# POWER_GEN.net
KiCad netlist of a schematic drawn in Altium Designer
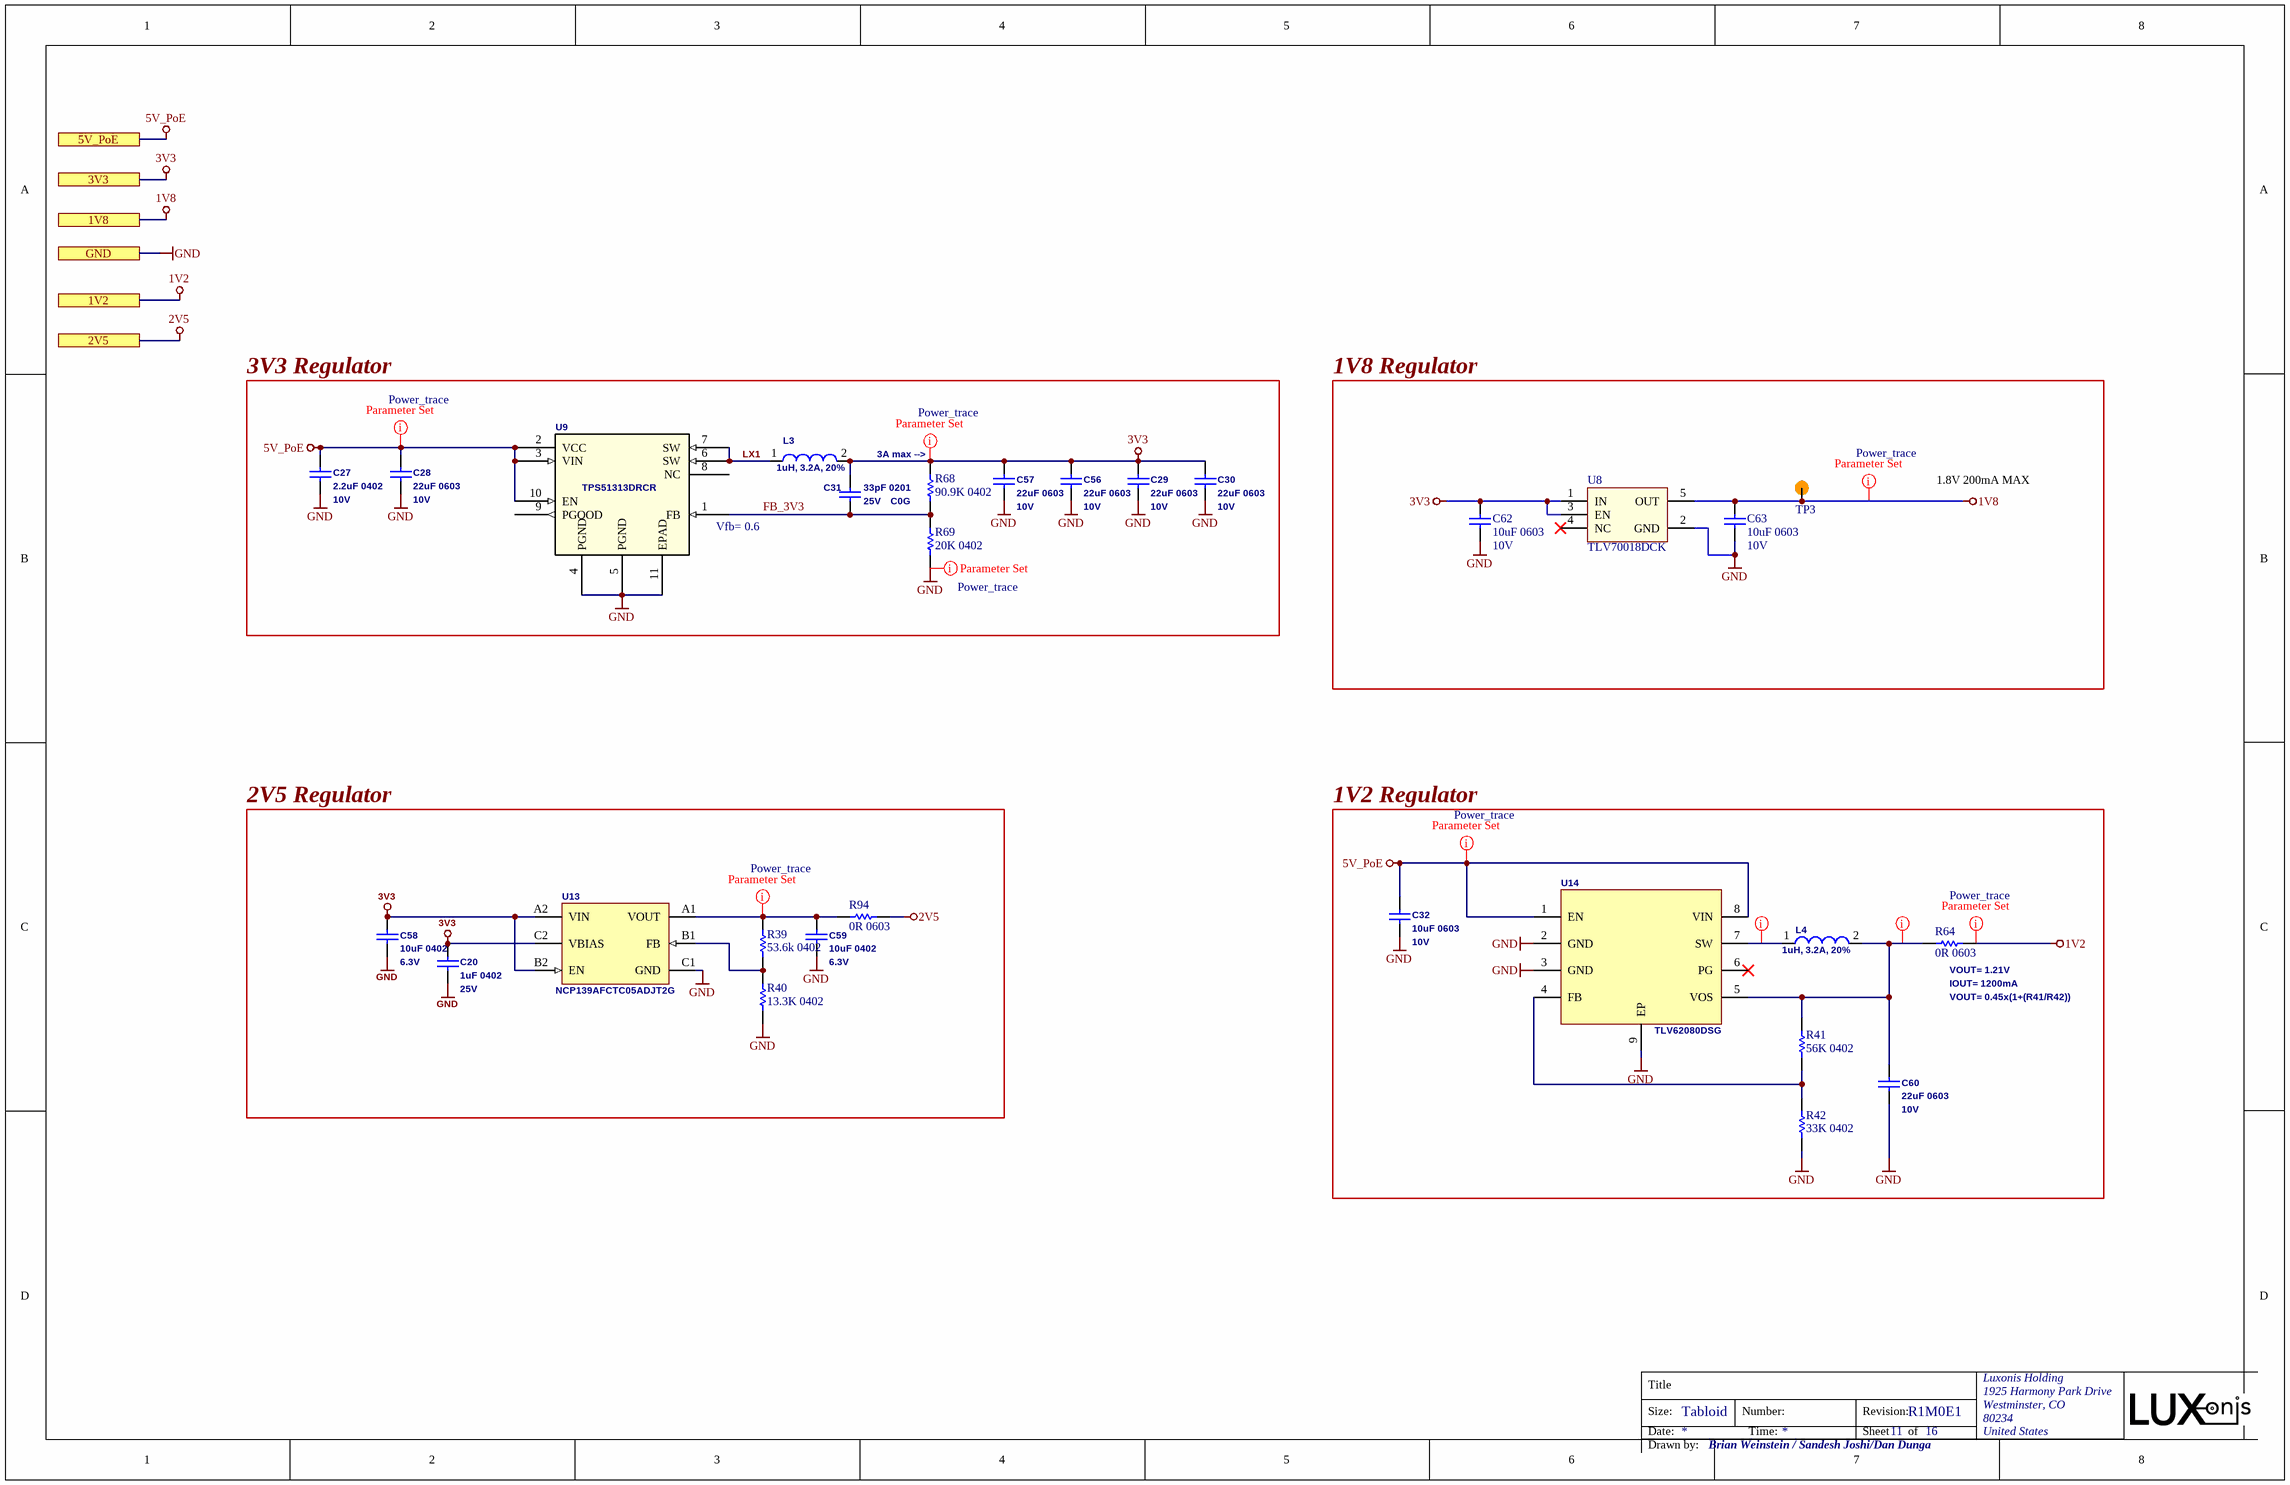
[diagram p0: POWER_GEN.SchDoc]

(export (version "E")
  (design (tool "Eeschema 10.0.6"))
  (components
    (comp (ref "C20")
      (value "1uF 0402")
      (footprint "CAP_Altium_Vault_Generic:CAPC0402(1005)70_L")
      (description "CAP CER 1UF 25V X5R 0402 10%")
      (fields
        (field (name "TOLERANCE") "10%")
        (field (name "VOLTAGE RATING") "25V")
        (field (name "VOLTAGE") "25V")
      )
      (libsource (lib "LuxonisMaster") (part "GRM155R61E105KA12D"))
    )
    (comp (ref "C27")
      (value "2.2uF 0402")
      (footprint "CAP_Altium_Vault_Generic:CAPC0402(1005)70_L")
      (description "CAP CER 2.2UF 10V X5R 0402 10%")
      (fields (field (name "TOLERANCE") "10%") (field (name "VOLTAGE RATING") "10V"))
      (libsource (lib "LuxonisMaster") (part "GRM155R61A225KE95D"))
    )
    (comp (ref "C28")
      (value "22uF 0603")
      (footprint "CAP_Altium_Vault_Generic:CAPC0603(1608)100_L")
      (description "CAP CER 22UF 10V X5R 0603 20%")
      (fields (field (name "TOLERANCE") "20%") (field (name "VOLTAGE RATING") "10V"))
      (libsource (lib "LuxonisMaster") (part "GRM188R61A226ME15D"))
    )
    (comp (ref "C29")
      (value "22uF 0603")
      (footprint "CAP_Altium_Vault_Generic:CAPC0603(1608)100_L")
      (description "CAP CER 22UF 10V X5R 0603 20%")
      (fields (field (name "TOLERANCE") "20%") (field (name "VOLTAGE RATING") "10V"))
      (libsource (lib "LuxonisMaster") (part "GRM188R61A226ME15D"))
    )
    (comp (ref "C30")
      (value "22uF 0603")
      (footprint "CAP_Altium_Vault_Generic:CAPC0603(1608)100_L")
      (description "CAP CER 22UF 10V X5R 0603 20%")
      (fields (field (name "TOLERANCE") "20%") (field (name "VOLTAGE RATING") "10V"))
      (libsource (lib "LuxonisMaster") (part "GRM188R61A226ME15D"))
    )
    (comp (ref "C31")
      (value "33pF 0201")
      (footprint "CAP_Altium_Vault_Generic:CAPC0201(0603)33_L")
      (description "CAP CER 33PF 25V C0G/NP0 0201")
      (fields
        (field (name "TOLERANCE") "5%")
        (field (name "VOLTAGE RATING") "25V")
        (field (name "DIELECTRIC") "C0G")
      )
      (libsource (lib "LuxonisMaster") (part "GRM0335C1E330JA01D"))
    )
    (comp (ref "C32")
      (value "10uF 0603")
      (footprint "CAP_Altium_Vault_Generic:CAPC0603(1608)100_L")
      (description "CAP CER 10UF 10V X5R 0603 20%")
      (fields (field (name "TOLERANCE") "20%") (field (name "VOLTAGE RATING") "10V"))
      (libsource (lib "LuxonisMaster") (part "GRM188R61A106ME69D"))
    )
    (comp (ref "C56")
      (value "22uF 0603")
      (footprint "CAP_Altium_Vault_Generic:CAPC0603(1608)100_L")
      (description "CAP CER 22UF 10V X5R 0603 20%")
      (fields (field (name "TOLERANCE") "20%") (field (name "VOLTAGE RATING") "10V"))
      (libsource (lib "LuxonisMaster") (part "GRM188R61A226ME15D"))
    )
    (comp (ref "C57")
      (value "22uF 0603")
      (footprint "CAP_Altium_Vault_Generic:CAPC0603(1608)100_L")
      (description "CAP CER 22UF 10V X5R 0603 20%")
      (fields (field (name "TOLERANCE") "20%") (field (name "VOLTAGE RATING") "10V"))
      (libsource (lib "LuxonisMaster") (part "GRM188R61A226ME15D"))
    )
    (comp (ref "C58")
      (value "10uF 0402")
      (footprint "CAP_Altium_Vault_Generic:CAPC0402(1005)70_L")
      (description "CAP CER 10UF 6.3V X5R 0402 20%")
      (fields (field (name "TOLERANCE") "20%") (field (name "VOLTAGE RATING") "6.3V"))
      (libsource (lib "LuxonisMaster") (part "GRM155R60J106ME15D"))
    )
    (comp (ref "C59")
      (value "10uF 0402")
      (footprint "CAP_Altium_Vault_Generic:CAPC0402(1005)70_L")
      (description "CAP CER 10UF 6.3V X5R 0402 20%")
      (fields (field (name "TOLERANCE") "20%") (field (name "VOLTAGE RATING") "6.3V"))
      (libsource (lib "LuxonisMaster") (part "GRM155R60J106ME15D"))
    )
    (comp (ref "C60")
      (value "22uF 0603")
      (footprint "CAP_Altium_Vault_Generic:CAPC0603(1608)100_L")
      (description "CAP CER 22UF 10V X5R 0603 20%")
      (fields (field (name "TOLERANCE") "20%") (field (name "VOLTAGE RATING") "10V"))
      (libsource (lib "LuxonisMaster") (part "GRM188R61A226ME15D"))
    )
    (comp (ref "C62")
      (value "10uF 0603")
      (footprint "CAP_Altium_Vault_Generic:CAPC0603(1608)100_N")
      (description "CAP CER 10UF 10V X5R 0603 20%")
      (fields (field (name "TOLERANCE") "20%") (field (name "VOLTAGE RATING") "10V"))
      (libsource (lib "LuxonisMaster") (part "GRM188R61A106ME69D"))
    )
    (comp (ref "C63")
      (value "10uF 0603")
      (footprint "CAP_Altium_Vault_Generic:CAPC0603(1608)100_N")
      (description "CAP CER 10UF 10V X5R 0603 20%")
      (fields (field (name "TOLERANCE") "20%") (field (name "VOLTAGE RATING") "10V"))
      (libsource (lib "LuxonisMaster") (part "GRM188R61A106ME69D"))
    )
    (comp (ref "L3")
      (value "1uH, 3.2A, 20%")
      (footprint "LuxonisMaster:DFE252012P-1R0M=P2")
      (description "FIXED IND 1UH 3.2A 42 MOHM SMD")
      (fields
        (field (name "MANUFACTURER") "Murata")
        (field (name "MANUFACTURER PART NUMBER") "DFE252012P-1R0M=P2")
      )
      (libsource (lib "LuxonisMaster") (part "DFE252012P-1R0M=P2"))
    )
    (comp (ref "L4")
      (value "1uH, 3.2A, 20%")
      (footprint "LuxonisMaster:DFE252012P-1R0M=P2")
      (description "FIXED IND 1UH 3.2A 42 MOHM SMD")
      (fields
        (field (name "MANUFACTURER") "Murata")
        (field (name "MANUFACTURER PART NUMBER") "DFE252012P-1R0M=P2")
      )
      (libsource (lib "LuxonisMaster") (part "DFE252012P-1R0M=P2"))
    )
    (comp (ref "R39")
      (value "53.6k 0402")
      (footprint "RES_Altium_Vault_Generic:RESC0402(1005)_L")
      (description "RES SMD 53.6K OHM 1% 1/16W 0402")
      (fields (field (name "TOLERANCE") "1%"))
      (libsource (lib "LuxonisMaster") (part "CRCW040253K6FKED"))
    )
    (comp (ref "R40")
      (value "13.3K 0402")
      (footprint "RES_Altium_Vault_Generic:RESC0402(1005)_L")
      (description "RES SMD 13.3K OHM 1% 1/16W 0402")
      (fields (field (name "TOLERANCE") "1%"))
      (libsource (lib "LuxonisMaster") (part "RC0402FR-0713K3L"))
    )
    (comp (ref "R41")
      (value "56K 0402")
      (footprint "RES_Altium_Vault_Generic:RESC0402(1005)_L")
      (fields
        (field (name "MANUFACTURER") "Yageo")
        (field (name "MANUFACTURER PART NUMBER") "RC0402FR-0756KL")
        (field (name "TOLERANCE") "1%")
      )
      (libsource (lib "LuxonisMaster") (part "RC0402FR-0756KL"))
    )
    (comp (ref "R42")
      (value "33K 0402")
      (footprint "RES_Altium_Vault_Generic:RESC0402(1005)_L")
      (description "RES SMD 33K OHM 1% 1/16W 0402")
      (fields (field (name "TOLERANCE") "1%"))
      (libsource (lib "LuxonisMaster") (part "CRCW040233K0FKED"))
    )
    (comp (ref "R64")
      (value "0R 0603")
      (footprint "RES_Altium_Vault_Generic:RESC0603(1608)_N")
      (description "RES SMD 0.0R OHM 1% 1/10W 0603")
      (fields (field (name "TOLERANCE") "5%"))
      (libsource (lib "LuxonisMaster") (part "CRCW06030000Z0EA"))
    )
    (comp (ref "R68")
      (value "90.9K 0402")
      (footprint "RES_Altium_Vault_Generic:RESC0402(1005)_L")
      (description "RES SMD 90.9K OHM 1% 1/16W 0402")
      (fields (field (name "TOLERANCE") "1%"))
      (libsource (lib "LuxonisMaster") (part "CRCW040290K9FKED"))
    )
    (comp (ref "R69")
      (value "20K 0402")
      (footprint "RES_Altium_Vault_Generic:RESC0402(1005)_L")
      (fields
        (field (name "MANUFACTURER") "Yageo")
        (field (name "MANUFACTURER PART NUMBER") "RC0402FR-0720KL")
        (field (name "TOLERANCE") "1%")
      )
      (libsource (lib "LuxonisMaster") (part "RC0402FR-0720KL"))
    )
    (comp (ref "R94")
      (value "0R 0603")
      (footprint "RES_Altium_Vault_Generic:RESC0603(1608)_N")
      (description "RES SMD 0.0R OHM 1% 1/10W 0603")
      (fields (field (name "TOLERANCE") "5%"))
      (libsource (lib "LuxonisMaster") (part "CRCW06030000Z0EA"))
    )
    (comp (ref "TP3")
      (value "TP100_200_NS")
      (footprint "TP100_200_NS")
      (libsource (lib "LuxonisMaster") (part "TEST_POINT"))
    )
    (comp (ref "U8")
      (value "TLV70018DCK")
      (footprint "TLV70018DCK")
      (description "IC REG LINEAR 1.8V 200MA SC70-5 Linear Voltage Regulator IC  1 Output  200mA SC-70-5")
      (libsource (lib "LuxonisMaster") (part "TLV70018DCK"))
    )
    (comp (ref "U9")
      (value "TPS51313DRCR")
      (footprint "VSON-TPS51313DRCR")
      (description "Switching Regulator, Voltage-mode, 3A, 1000kHz Switching Freq-Max, PDSO10")
      (libsource (lib "LuxonisMaster") (part "TPS51313DRCR"))
    )
    (comp (ref "U13")
      (value "NCP139AFCTC05ADJT2G")
      (footprint "NCP139AFCTC05ADJT2G")
      (description "IC REG LINEAR POS ADJ 1A 6WLCSP")
      (fields (field (name "OCTOPART") "https://octopart.com/ncp139afctc05adjt2g-on+semiconductor-77040756"))
      (libsource (lib "LuxonisMaster") (part "NCP139AFCTC05ADJT2G"))
    )
    (comp (ref "U14")
      (value "TLV62080DSG")
      (footprint "LuxonisMaster:TLV62080DSG")
      (description "IC REG BUCK ADJ 1.2A SYNC 8WSON")
      (libsource (lib "LuxonisMaster") (part "TLV62080DSG"))
    )
  )
  (nets
    (net (code "1") (name "/FB_3V3") (class "Default")
      (node (ref "C31") (pin "1") (pinfunction "1_1") (pintype "passive"))
      (node (ref "R68") (pin "1") (pinfunction "1_1") (pintype "passive"))
      (node (ref "R69") (pin "2") (pinfunction "2_2") (pintype "passive"))
      (node (ref "U9") (pin "1") (pinfunction "FB_1") (pintype "input"))
    )
    (net (code "2") (name "/LX1") (class "Default")
      (node (ref "L3") (pin "1") (pinfunction "1_1") (pintype "passive"))
      (node (ref "U9") (pin "6") (pinfunction "SW_6") (pintype "input"))
      (node (ref "U9") (pin "7") (pinfunction "SW_7") (pintype "input"))
    )
    (net (code "3") (name "1V2") (class "Default")
      (node (ref "R64") (pin "2") (pinfunction "2_2") (pintype "passive"))
    )
    (net (code "4") (name "1V8") (class "Default")
      (node (ref "C63") (pin "2") (pinfunction "2_2") (pintype "passive"))
      (node (ref "TP3") (pin "1") (pintype "passive"))
      (node (ref "U8") (pin "5") (pinfunction "OUT_5") (pintype "passive"))
    )
    (net (code "5") (name "2V5") (class "Default")
      (node (ref "R94") (pin "2") (pinfunction "2_2") (pintype "passive"))
    )
    (net (code "6") (name "3V3") (class "Default")
      (node (ref "C20") (pin "1") (pinfunction "1_1") (pintype "passive"))
      (node (ref "C29") (pin "1") (pinfunction "1_1") (pintype "passive"))
      (node (ref "C30") (pin "1") (pinfunction "1_1") (pintype "passive"))
      (node (ref "C31") (pin "2") (pinfunction "2_2") (pintype "passive"))
      (node (ref "C56") (pin "1") (pinfunction "1_1") (pintype "passive"))
      (node (ref "C57") (pin "1") (pinfunction "1_1") (pintype "passive"))
      (node (ref "C58") (pin "2") (pinfunction "2_2") (pintype "passive"))
      (node (ref "C62") (pin "2") (pinfunction "2_2") (pintype "passive"))
      (node (ref "L3") (pin "2") (pinfunction "2_2") (pintype "passive"))
      (node (ref "R68") (pin "2") (pinfunction "2_2") (pintype "passive"))
      (node (ref "U13") (pin "A2") (pinfunction "VIN_A2") (pintype "power_in"))
      (node (ref "U13") (pin "B2") (pinfunction "EN_B2") (pintype "input"))
      (node (ref "U13") (pin "C2") (pinfunction "VBIAS_C2") (pintype "power_in"))
      (node (ref "U8") (pin "1") (pinfunction "IN_1") (pintype "passive"))
      (node (ref "U8") (pin "3") (pinfunction "EN_3") (pintype "passive"))
    )
    (net (code "7") (name "5V_PoE") (class "Default")
      (node (ref "C27") (pin "1") (pinfunction "1_1") (pintype "passive"))
      (node (ref "C28") (pin "1") (pinfunction "1_1") (pintype "passive"))
      (node (ref "C32") (pin "2") (pinfunction "2_2") (pintype "passive"))
      (node (ref "U14") (pin "1") (pinfunction "EN_1") (pintype "passive"))
      (node (ref "U14") (pin "8") (pinfunction "VIN_8") (pintype "passive"))
      (node (ref "U9") (pin "10") (pinfunction "EN_10") (pintype "input"))
      (node (ref "U9") (pin "2") (pinfunction "VCC_2") (pintype "power_in"))
      (node (ref "U9") (pin "3") (pinfunction "VIN_3") (pintype "input"))
    )
    (net (code "8") (name "GND") (class "Default")
      (node (ref "C20") (pin "2") (pinfunction "2_2") (pintype "passive"))
      (node (ref "C27") (pin "2") (pinfunction "2_2") (pintype "passive"))
      (node (ref "C28") (pin "2") (pinfunction "2_2") (pintype "passive"))
      (node (ref "C29") (pin "2") (pinfunction "2_2") (pintype "passive"))
      (node (ref "C30") (pin "2") (pinfunction "2_2") (pintype "passive"))
      (node (ref "C32") (pin "1") (pinfunction "1_1") (pintype "passive"))
      (node (ref "C56") (pin "2") (pinfunction "2_2") (pintype "passive"))
      (node (ref "C57") (pin "2") (pinfunction "2_2") (pintype "passive"))
      (node (ref "C58") (pin "1") (pinfunction "1_1") (pintype "passive"))
      (node (ref "C59") (pin "1") (pinfunction "1_1") (pintype "passive"))
      (node (ref "C60") (pin "1") (pinfunction "1_1") (pintype "passive"))
      (node (ref "C62") (pin "1") (pinfunction "1_1") (pintype "passive"))
      (node (ref "C63") (pin "1") (pinfunction "1_1") (pintype "passive"))
      (node (ref "R40") (pin "1") (pinfunction "1_1") (pintype "passive"))
      (node (ref "R42") (pin "1") (pinfunction "1_1") (pintype "passive"))
      (node (ref "R69") (pin "1") (pinfunction "1_1") (pintype "passive"))
      (node (ref "U13") (pin "C1") (pinfunction "GND_C1") (pintype "power_in"))
      (node (ref "U14") (pin "2") (pinfunction "GND_2") (pintype "passive"))
      (node (ref "U14") (pin "3") (pinfunction "GND_3") (pintype "passive"))
      (node (ref "U14") (pin "9") (pinfunction "EP_9") (pintype "passive"))
      (node (ref "U8") (pin "2") (pinfunction "GND_2") (pintype "passive"))
      (node (ref "U9") (pin "11") (pinfunction "EPAD_11") (pintype "passive"))
      (node (ref "U9") (pin "4") (pinfunction "PGND_4") (pintype "power_in"))
      (node (ref "U9") (pin "5") (pinfunction "PGND_5") (pintype "power_in"))
    )
    (net (code "9") (name "Net-(U13-FB)") (class "Default")
      (node (ref "R39") (pin "1") (pinfunction "1_1") (pintype "passive"))
      (node (ref "R40") (pin "2") (pinfunction "2_2") (pintype "passive"))
      (node (ref "U13") (pin "B1") (pinfunction "FB_B1") (pintype "input"))
    )
    (net (code "10") (name "Net-(U13-VOUT)") (class "Default")
      (node (ref "C59") (pin "2") (pinfunction "2_2") (pintype "passive"))
      (node (ref "R39") (pin "2") (pinfunction "2_2") (pintype "passive"))
      (node (ref "R94") (pin "1") (pinfunction "1_1") (pintype "passive"))
      (node (ref "U13") (pin "A1") (pinfunction "VOUT_A1") (pintype "power_in"))
    )
    (net (code "11") (name "Net-(U14-FB)") (class "Default")
      (node (ref "R41") (pin "1") (pinfunction "1_1") (pintype "passive"))
      (node (ref "R42") (pin "2") (pinfunction "2_2") (pintype "passive"))
      (node (ref "U14") (pin "4") (pinfunction "FB_4") (pintype "passive"))
    )
    (net (code "12") (name "Net-(U14-SW)") (class "Default")
      (node (ref "L4") (pin "1") (pinfunction "1_1") (pintype "passive"))
      (node (ref "U14") (pin "7") (pinfunction "SW_7") (pintype "passive"))
    )
    (net (code "13") (name "Net-(U14-VOS)") (class "Default")
      (node (ref "C60") (pin "2") (pinfunction "2_2") (pintype "passive"))
      (node (ref "L4") (pin "2") (pinfunction "2_2") (pintype "passive"))
      (node (ref "R41") (pin "2") (pinfunction "2_2") (pintype "passive"))
      (node (ref "R64") (pin "1") (pinfunction "1_1") (pintype "passive"))
      (node (ref "U14") (pin "5") (pinfunction "VOS_5") (pintype "passive"))
    )
    (net (code "14") (name "unconnected-(U8-NC-Pad4)") (class "Default")
      (node (ref "U8") (pin "4") (pinfunction "NC_4") (pintype "passive+no_connect"))
    )
    (net (code "15") (name "unconnected-(U9-NC-Pad8)") (class "Default")
      (node (ref "U9") (pin "8") (pinfunction "NC_8") (pintype "passive"))
    )
    (net (code "16") (name "unconnected-(U9-PGOOD-Pad9)") (class "Default")
      (node (ref "U9") (pin "9") (pinfunction "PGOOD_9") (pintype "output"))
    )
    (net (code "17") (name "unconnected-(U14-PG-Pad6)") (class "Default")
      (node (ref "U14") (pin "6") (pinfunction "PG_6") (pintype "passive+no_connect"))
    )
  )
)
